# Display.net
KiCad netlist of a schematic drawn in Altium Designer
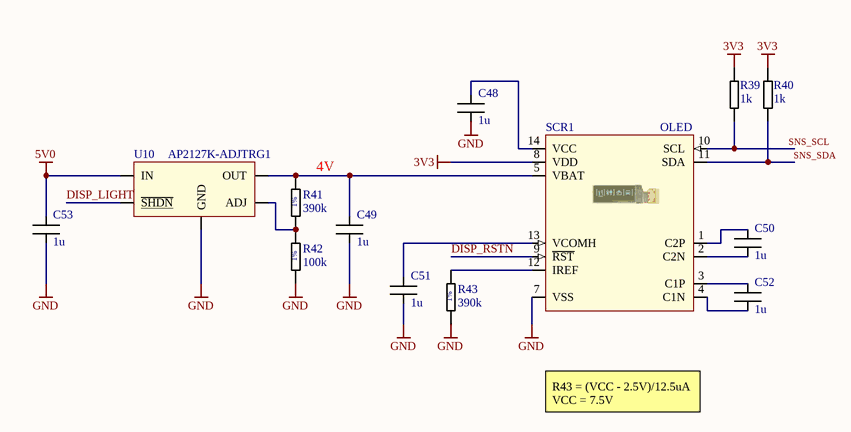
[diagram p0: Display.SchDoc]

(export (version "E")
  (design (tool "Eeschema 10.0.6"))
  (components
    (comp (ref "C48")
      (value "1u")
      (footprint "CAPC1608N")
      (description "0603 imperial SMD Capacitor")
      (fields (field (name "TOLERANCE") "10%") (field (name "Comment") "Capacitor"))
      (libsource (lib "RLC") (part "Capacitor"))
    )
    (comp (ref "C49")
      (value "1u")
      (footprint "CAPC1608N")
      (description "0603 imperial SMD Capacitor")
      (fields (field (name "TOLERANCE") "10%") (field (name "Comment") "Capacitor"))
      (libsource (lib "RLC") (part "Capacitor"))
    )
    (comp (ref "C50")
      (value "1u")
      (footprint "CAPC1608N")
      (description "0603 imperial SMD Capacitor")
      (fields (field (name "TOLERANCE") "10%") (field (name "Comment") "Capacitor"))
      (libsource (lib "RLC") (part "Capacitor"))
    )
    (comp (ref "C51")
      (value "1u")
      (footprint "CAPC1608N")
      (description "0603 imperial SMD Capacitor")
      (fields (field (name "TOLERANCE") "10%") (field (name "Comment") "Capacitor"))
      (libsource (lib "RLC") (part "Capacitor"))
    )
    (comp (ref "C52")
      (value "1u")
      (footprint "CAPC1608N")
      (description "0603 imperial SMD Capacitor")
      (fields (field (name "TOLERANCE") "10%") (field (name "Comment") "Capacitor"))
      (libsource (lib "RLC") (part "Capacitor"))
    )
    (comp (ref "C53")
      (value "1u")
      (footprint "CAPC1608N")
      (description "0603 imperial SMD Capacitor")
      (fields (field (name "TOLERANCE") "10%") (field (name "Comment") "Capacitor"))
      (libsource (lib "RLC") (part "Capacitor"))
    )
    (comp (ref "R39")
      (value "1k")
      (footprint "RESC1005N")
      (description "0402 Film SMD Resistor")
      (fields (field (name "TOLERANCE") "1%") (field (name "POWER") "0.1W"))
      (libsource (lib "RLC") (part "Resistor"))
    )
    (comp (ref "R40")
      (value "1k")
      (footprint "RESC1005N")
      (description "0402 Film SMD Resistor")
      (fields (field (name "TOLERANCE") "1%") (field (name "POWER") "0.1W"))
      (libsource (lib "RLC") (part "Resistor"))
    )
    (comp (ref "R41")
      (value "390k")
      (footprint "RESC1005N")
      (description "0402 Film SMD Resistor")
      (fields
        (field (name "TOLERANCE") "1%")
        (field (name "POWER") "63mW")
        (field (name "Comment") "Resistor")
      )
      (libsource (lib "RLC") (part "Resistor"))
    )
    (comp (ref "R42")
      (value "100k")
      (footprint "RESC1005N")
      (description "0402 Film SMD Resistor")
      (fields
        (field (name "TOLERANCE") "1%")
        (field (name "POWER") "63mW")
        (field (name "Comment") "Resistor")
      )
      (libsource (lib "RLC") (part "Resistor"))
    )
    (comp (ref "R43")
      (value "390k")
      (footprint "RESC1005N")
      (description "0402 Film SMD Resistor")
      (fields
        (field (name "TOLERANCE") "1%")
        (field (name "POWER") "63mW")
        (field (name "Comment") "Resistor")
      )
      (libsource (lib "RLC") (part "Resistor"))
    )
    (comp (ref "SCR1")
      (value "OLED")
      (footprint "REX012832FSPP3N00000")
      (description "Wyświetlacz: OLED; graficzny; 0,91\"; 128x32; Wym:30x11,5x1,45mm")
      (libsource (lib "Raystar_Optronics") (part "REX012832FSPP3N00000"))
    )
    (comp (ref "U10")
      (value "AP2127K-ADJTRG1")
      (footprint "SOT-23-5")
      (description "0.4A, 0.8-5.5V, linear LDO, adjustable, SOT-23-5 package")
      (libsource (lib "Diodes Incorporated PMIC") (part "AP2127K-ADJTRG1"))
    )
  )
  (nets
    (net (code "1") (name "/DISP_LIGHT") (class "Default")
      (node (ref "U10") (pin "3") (pinfunction "SHDN_3") (pintype "passive"))
    )
    (net (code "2") (name "/DISP_RSTN") (class "Default")
      (node (ref "SCR1") (pin "9") (pinfunction "~{RST}_9") (pintype "input"))
    )
    (net (code "3") (name "/SNS_SCL") (class "Default")
      (node (ref "R39") (pin "2") (pinfunction "2_2") (pintype "passive"))
      (node (ref "SCR1") (pin "10") (pinfunction "SCL_10") (pintype "input"))
    )
    (net (code "4") (name "/SNS_SDA") (class "Default")
      (node (ref "R40") (pin "2") (pinfunction "2_2") (pintype "passive"))
      (node (ref "SCR1") (pin "11") (pinfunction "SDA_11") (pintype "bidirectional"))
    )
    (net (code "5") (name "3V3") (class "Default")
      (node (ref "R39") (pin "1") (pinfunction "1_1") (pintype "passive"))
      (node (ref "R40") (pin "1") (pinfunction "1_1") (pintype "passive"))
      (node (ref "SCR1") (pin "8") (pinfunction "VDD_8") (pintype "power_in"))
    )
    (net (code "6") (name "5V0") (class "Default")
      (node (ref "C53") (pin "2") (pinfunction "2_2") (pintype "passive"))
      (node (ref "U10") (pin "1") (pinfunction "IN_1") (pintype "power_in"))
    )
    (net (code "7") (name "GND") (class "Default")
      (node (ref "C48") (pin "1") (pinfunction "1_1") (pintype "passive"))
      (node (ref "C49") (pin "1") (pinfunction "1_1") (pintype "passive"))
      (node (ref "C51") (pin "1") (pinfunction "1_1") (pintype "passive"))
      (node (ref "C53") (pin "1") (pinfunction "1_1") (pintype "passive"))
      (node (ref "R42") (pin "2") (pinfunction "2_2") (pintype "passive"))
      (node (ref "R43") (pin "2") (pinfunction "2_2") (pintype "passive"))
      (node (ref "SCR1") (pin "7") (pinfunction "VSS_7") (pintype "power_in"))
      (node (ref "U10") (pin "2") (pinfunction "GND_2") (pintype "passive"))
    )
    (net (code "8") (name "Net-(SCR1-C1N)") (class "Default")
      (node (ref "C52") (pin "1") (pinfunction "1_1") (pintype "passive"))
      (node (ref "SCR1") (pin "4") (pinfunction "C1N_4") (pintype "passive"))
    )
    (net (code "9") (name "Net-(SCR1-C1P)") (class "Default")
      (node (ref "C52") (pin "2") (pinfunction "2_2") (pintype "passive"))
      (node (ref "SCR1") (pin "3") (pinfunction "C1P_3") (pintype "passive"))
    )
    (net (code "10") (name "Net-(SCR1-C2N)") (class "Default")
      (node (ref "C50") (pin "1") (pinfunction "1_1") (pintype "passive"))
      (node (ref "SCR1") (pin "2") (pinfunction "C2N_2") (pintype "passive"))
    )
    (net (code "11") (name "Net-(SCR1-C2P)") (class "Default")
      (node (ref "C50") (pin "2") (pinfunction "2_2") (pintype "passive"))
      (node (ref "SCR1") (pin "1") (pinfunction "C2P_1") (pintype "passive"))
    )
    (net (code "12") (name "Net-(SCR1-IREF)") (class "Default")
      (node (ref "R43") (pin "1") (pinfunction "1_1") (pintype "passive"))
      (node (ref "SCR1") (pin "12") (pinfunction "IREF_12") (pintype "passive"))
    )
    (net (code "13") (name "Net-(SCR1-VBAT)") (class "Default")
      (node (ref "C49") (pin "2") (pinfunction "2_2") (pintype "passive"))
      (node (ref "R41") (pin "1") (pinfunction "1_1") (pintype "passive"))
      (node (ref "SCR1") (pin "5") (pinfunction "VBAT_5") (pintype "power_in"))
      (node (ref "U10") (pin "5") (pinfunction "OUT_5") (pintype "passive"))
    )
    (net (code "14") (name "Net-(SCR1-VCC)") (class "Default")
      (node (ref "C48") (pin "2") (pinfunction "2_2") (pintype "passive"))
      (node (ref "SCR1") (pin "14") (pinfunction "VCC_14") (pintype "power_in"))
    )
    (net (code "15") (name "Net-(SCR1-VCOMH)") (class "Default")
      (node (ref "C51") (pin "2") (pinfunction "2_2") (pintype "passive"))
      (node (ref "SCR1") (pin "13") (pinfunction "VCOMH_13") (pintype "input"))
    )
    (net (code "16") (name "Net-(U10-ADJ)") (class "Default")
      (node (ref "R41") (pin "2") (pinfunction "2_2") (pintype "passive"))
      (node (ref "R42") (pin "1") (pinfunction "1_1") (pintype "passive"))
      (node (ref "U10") (pin "4") (pinfunction "ADJ_4") (pintype "passive"))
    )
  )
)
